# 0805_0603_0402.net
KiCad netlist of a schematic drawn in EAGLE
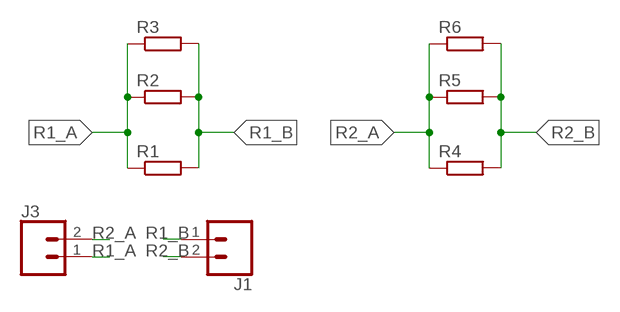
[diagram p0: schematic, sheet 1]

(export (version "E")
  (design (tool "Eeschema 10.0.6"))
  (components
    (comp (ref "J1")
      (value "CONN_02")
      (footprint "eagle-import:1X02")
      (libsource (lib "eagle-import") (part "CONN_02"))
    )
    (comp (ref "J3")
      (value "CONN_02")
      (footprint "eagle-import:1X02")
      (libsource (lib "eagle-import") (part "CONN_02"))
    )
    (comp (ref "R1")
      (value "R-EU_R0805")
      (footprint "eagle-import:R0805")
      (libsource (lib "eagle-import") (part "R-EU_R0805"))
    )
    (comp (ref "R2")
      (value "R-EU_R0603")
      (footprint "eagle-import:R0603")
      (fields (field (name "MF") "Yageo"))
      (libsource (lib "eagle-import") (part "R-EU_R0603"))
    )
    (comp (ref "R3")
      (value "R-EU_R0402")
      (footprint "eagle-import:R0402")
      (fields (field (name "MF") "Yageo"))
      (libsource (lib "eagle-import") (part "R-EU_R0402"))
    )
    (comp (ref "R4")
      (value "R-EU_R0805")
      (footprint "eagle-import:R0805")
      (libsource (lib "eagle-import") (part "R-EU_R0805"))
    )
    (comp (ref "R5")
      (value "R-EU_R0603")
      (footprint "eagle-import:R0603")
      (fields (field (name "MF") "Yageo"))
      (libsource (lib "eagle-import") (part "R-EU_R0603"))
    )
    (comp (ref "R6")
      (value "R-EU_R0402")
      (footprint "eagle-import:R0402")
      (fields (field (name "MF") "Yageo"))
      (libsource (lib "eagle-import") (part "R-EU_R0402"))
    )
  )
  (nets
    (net (code "1") (name "R1_A") (class "Default")
      (node (ref "J3") (pin "1") (pinfunction "1_1") (pintype "passive"))
      (node (ref "R1") (pin "1") (pinfunction "1_1") (pintype "passive"))
      (node (ref "R2") (pin "1") (pinfunction "1_1") (pintype "passive"))
      (node (ref "R3") (pin "1") (pinfunction "1_1") (pintype "passive"))
    )
    (net (code "2") (name "R1_B") (class "Default")
      (node (ref "J1") (pin "1") (pinfunction "1_1") (pintype "passive"))
      (node (ref "R1") (pin "2") (pinfunction "2_2") (pintype "passive"))
      (node (ref "R2") (pin "2") (pinfunction "2_2") (pintype "passive"))
      (node (ref "R3") (pin "2") (pinfunction "2_2") (pintype "passive"))
    )
    (net (code "3") (name "R2_A") (class "Default")
      (node (ref "J3") (pin "2") (pinfunction "2_2") (pintype "passive"))
      (node (ref "R4") (pin "1") (pinfunction "1_1") (pintype "passive"))
      (node (ref "R5") (pin "1") (pinfunction "1_1") (pintype "passive"))
      (node (ref "R6") (pin "1") (pinfunction "1_1") (pintype "passive"))
    )
    (net (code "4") (name "R2_B") (class "Default")
      (node (ref "J1") (pin "2") (pinfunction "2_2") (pintype "passive"))
      (node (ref "R4") (pin "2") (pinfunction "2_2") (pintype "passive"))
      (node (ref "R5") (pin "2") (pinfunction "2_2") (pintype "passive"))
      (node (ref "R6") (pin "2") (pinfunction "2_2") (pintype "passive"))
    )
  )
)
